# kill_switch-sch.net
KiCad netlist of a schematic drawn in Altium Designer
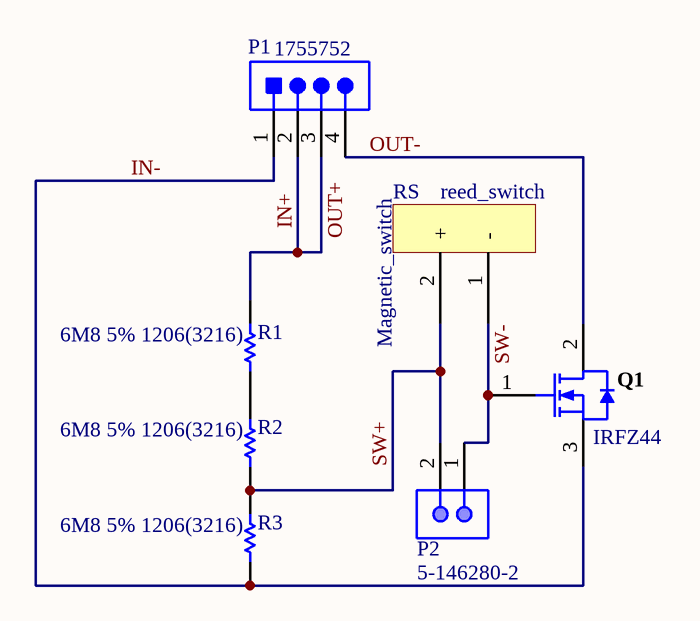
[diagram p0: kill_switch-sch.SchDoc]

(export (version "E")
  (design (tool "Eeschema 10.0.6"))
  (components
    (comp (ref "P1")
      (value "1755752")
      (footprint "PHOE-1755752-4_V")
      (fields (field (name "MANUFACTURER") "Phoenix Contact"))
      (libsource (lib "Altium Content Vault") (part "CN-1P-M-R4"))
    )
    (comp (ref "P2")
      (value "5-146280-2")
      (footprint "TECO-5-146280-2_V")
      (fields (field (name "MANUFACTURER") "TE Connectivity"))
      (libsource (lib "Altium Content Vault") (part "CN-1P-M-R2"))
    )
    (comp (ref "Q1")
      (value "IRFZ44")
      (footprint "VISH-TO-220AB-3_A")
      (description "Power MOSFET, 100 VDS, -55 to 175 degC, 3-Pin TO-220AB, RoHS, Tube")
      (fields (field (name "MANUFACTURER") "Vishay"))
      (libsource (lib "Altium Content Vault") (part "NEMOS-GDS-3"))
    )
    (comp (ref "R1")
      (value "6M8 5% 1206(3216)")
      (footprint "RESC1206(3216)_L")
      (description "6M8 0.25W 5% 1206 (3216 Metric)  SMD")
      (fields (field (name "TOLERANCE") "5 %") (field (name "POWER") "0.25 W"))
      (libsource (lib "Altium Content Vault") (part "RES"))
    )
    (comp (ref "R2")
      (value "6M8 5% 1206(3216)")
      (footprint "RESC1206(3216)_L")
      (description "6M8 0.25W 5% 1206 (3216 Metric)  SMD")
      (fields (field (name "TOLERANCE") "5 %") (field (name "POWER") "0.25 W"))
      (libsource (lib "Altium Content Vault") (part "RES"))
    )
    (comp (ref "R3")
      (value "6M8 5% 1206(3216)")
      (footprint "RESC1206(3216)_L")
      (description "6M8 0.25W 5% 1206 (3216 Metric)  SMD")
      (fields (field (name "TOLERANCE") "5 %") (field (name "POWER") "0.25 W"))
      (libsource (lib "Altium Content Vault") (part "RES"))
    )
    (comp (ref "RS")
      (value "Magnetic_switch")
      (footprint "Reed_switch")
      (fields (field (name "CATERGORIES") "reed_switch"))
      (libsource (lib "reed_switch") (part "Component_1"))
    )
  )
  (nets
    (net (code "1") (name "/IN+") (class "Default")
      (node (ref "P1") (pin "2") (pinfunction "2_2") (pintype "passive"))
      (node (ref "P1") (pin "3") (pinfunction "3_3") (pintype "passive"))
      (node (ref "R1") (pin "2") (pinfunction "2_2") (pintype "passive"))
    )
    (net (code "2") (name "/IN-") (class "Default")
      (node (ref "P1") (pin "1") (pinfunction "1_1") (pintype "passive"))
      (node (ref "Q1") (pin "3") (pinfunction "S_3") (pintype "passive"))
      (node (ref "R3") (pin "1") (pinfunction "1_1") (pintype "passive"))
    )
    (net (code "3") (name "/OUT-") (class "Default")
      (node (ref "P1") (pin "4") (pinfunction "4_4") (pintype "passive"))
      (node (ref "Q1") (pin "2") (pinfunction "D_2") (pintype "passive"))
    )
    (net (code "4") (name "/SW+") (class "Default")
      (node (ref "P2") (pin "2") (pinfunction "2_2") (pintype "passive"))
      (node (ref "R2") (pin "1") (pinfunction "1_1") (pintype "passive"))
      (node (ref "R3") (pin "2") (pinfunction "2_2") (pintype "passive"))
      (node (ref "RS") (pin "2") (pinfunction "+_2") (pintype "passive"))
    )
    (net (code "5") (name "/SW-") (class "Default")
      (node (ref "P2") (pin "1") (pinfunction "1_1") (pintype "passive"))
      (node (ref "Q1") (pin "1") (pinfunction "G_1") (pintype "passive"))
      (node (ref "RS") (pin "1") (pinfunction "-_1") (pintype "passive"))
    )
    (net (code "6") (name "Net-(R1-Pad1)") (class "Default")
      (node (ref "R1") (pin "1") (pinfunction "1_1") (pintype "passive"))
      (node (ref "R2") (pin "2") (pinfunction "2_2") (pintype "passive"))
    )
  )
)
